# mLRS-tx-dual-base-v031-np.net
KiCad netlist of a schematic drawn in EAGLE
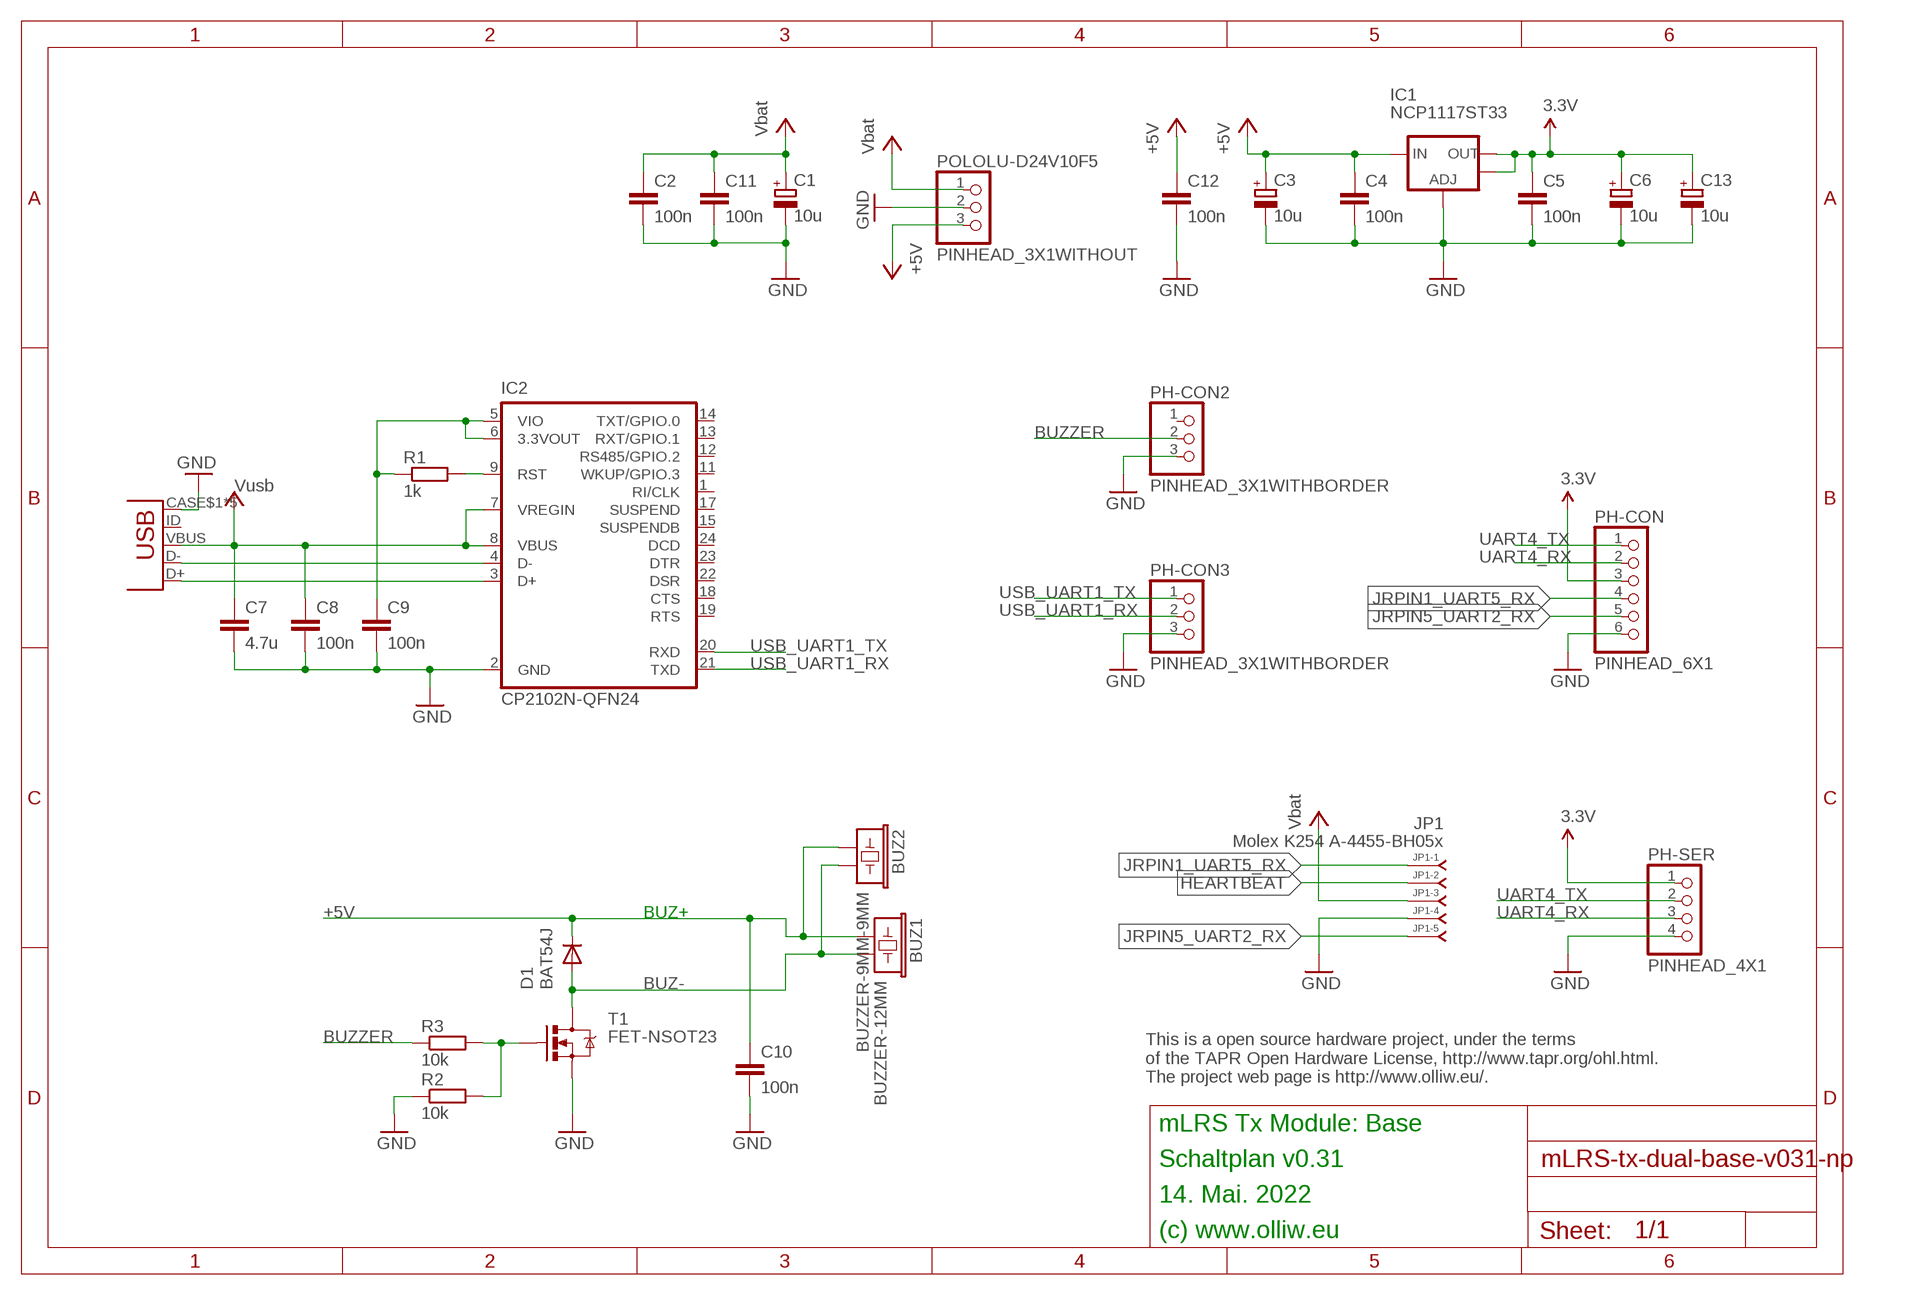
[diagram p0: schematic, sheet 1]

(export (version "E")
  (design (tool "Eeschema 10.0.6"))
  (components
    (comp (ref "BUZ1")
      (value "BUZZER-12MM")
      (footprint "eagle-import:BUZZER-12MM")
      (libsource (lib "eagle-import") (part "BUZZER-12MM"))
    )
    (comp (ref "BUZ2")
      (value "BUZZER-9MM-9MM")
      (footprint "eagle-import:BUZZER-9MM")
      (libsource (lib "eagle-import") (part "BUZZER-9MM-9MM"))
    )
    (comp (ref "C1")
      (value "10u")
      (footprint "eagle-import:SMC_A")
      (libsource (lib "eagle-import") (part "CPOL-EUSMCA"))
    )
    (comp (ref "C2")
      (value "100n")
      (footprint "eagle-import:C0603")
      (libsource (lib "eagle-import") (part "C-EUC0603"))
    )
    (comp (ref "C3")
      (value "10u")
      (footprint "eagle-import:SMC_A")
      (libsource (lib "eagle-import") (part "CPOL-EUSMCA"))
    )
    (comp (ref "C4")
      (value "100n")
      (footprint "eagle-import:C0603")
      (libsource (lib "eagle-import") (part "C-EUC0603"))
    )
    (comp (ref "C5")
      (value "100n")
      (footprint "eagle-import:C0603")
      (libsource (lib "eagle-import") (part "C-EUC0603"))
    )
    (comp (ref "C6")
      (value "10u")
      (footprint "eagle-import:SMC_A")
      (libsource (lib "eagle-import") (part "CPOL-EUSMCA"))
    )
    (comp (ref "C7")
      (value "4.7u")
      (footprint "eagle-import:C0603")
      (libsource (lib "eagle-import") (part "C-EUC0603"))
    )
    (comp (ref "C8")
      (value "100n")
      (footprint "eagle-import:C0402")
      (libsource (lib "eagle-import") (part "C-EUC0402"))
    )
    (comp (ref "C9")
      (value "100n")
      (footprint "eagle-import:C0402")
      (libsource (lib "eagle-import") (part "C-EUC0402"))
    )
    (comp (ref "C10")
      (value "100n")
      (footprint "eagle-import:C0402")
      (libsource (lib "eagle-import") (part "C-EUC0402"))
    )
    (comp (ref "C11")
      (value "100n")
      (footprint "eagle-import:C0603")
      (libsource (lib "eagle-import") (part "C-EUC0603"))
    )
    (comp (ref "C12")
      (value "100n")
      (footprint "eagle-import:C0603")
      (libsource (lib "eagle-import") (part "C-EUC0603"))
    )
    (comp (ref "C13")
      (value "10u")
      (footprint "eagle-import:SMC_A")
      (libsource (lib "eagle-import") (part "CPOL-EUSMCA"))
    )
    (comp (ref "D1")
      (value "BAT54J")
      (footprint "eagle-import:SOD110-R")
      (libsource (lib "eagle-import") (part "DIODE-SOD110-R"))
    )
    (comp (ref "IC1")
      (value "NCP1117ST33")
      (footprint "eagle-import:SOT223")
      (libsource (lib "eagle-import") (part "V_REG_LM1117SOT223"))
    )
    (comp (ref "IC2")
      (value "CP2102N-QFN24")
      (footprint "eagle-import:QFN24-CP2102N")
      (libsource (lib "eagle-import") (part "CP2102N-QFN24"))
    )
    (comp (ref "JP1")
      (value "Molex K254 A-4455-BH05x")
      (footprint "eagle-import:4455-B05")
      (libsource (lib "eagle-import") (part "4455-B05_S"))
    )
    (comp (ref "PH-CON")
      (value "PINHEAD_6X1")
      (footprint "eagle-import:PINHEAD_6X1")
      (libsource (lib "eagle-import") (part "PINHEAD_6X1"))
    )
    (comp (ref "PH-CON2")
      (value "PINHEAD_3X1WITHBORDER")
      (footprint "eagle-import:PINHEAD_3X1")
      (libsource (lib "eagle-import") (part "PINHEAD_3X1WITHBORDER"))
    )
    (comp (ref "PH-CON3")
      (value "PINHEAD_3X1WITHBORDER")
      (footprint "eagle-import:PINHEAD_3X1")
      (libsource (lib "eagle-import") (part "PINHEAD_3X1WITHBORDER"))
    )
    (comp (ref "PH-SER")
      (value "PINHEAD_4X1")
      (footprint "eagle-import:PINHEAD_4X1")
      (libsource (lib "eagle-import") (part "PINHEAD_4X1"))
    )
    (comp (ref "POLOLU-D24V10F5")
      (value "PINHEAD_3X1WITHOUT")
      (footprint "eagle-import:PINHEAD_3X1_WO")
      (libsource (lib "eagle-import") (part "PINHEAD_3X1WITHOUT"))
    )
    (comp (ref "R1")
      (value "1k")
      (footprint "eagle-import:R0402")
      (libsource (lib "eagle-import") (part "R-EU_R0402"))
    )
    (comp (ref "R2")
      (value "10k")
      (footprint "eagle-import:R0402")
      (libsource (lib "eagle-import") (part "R-EU_R0402"))
    )
    (comp (ref "R3")
      (value "10k")
      (footprint "eagle-import:R0402")
      (libsource (lib "eagle-import") (part "R-EU_R0402"))
    )
    (comp (ref "T1")
      (value "FET-NSOT23")
      (footprint "eagle-import:SOT23")
      (libsource (lib "eagle-import") (part "FET-NSOT23"))
    )
    (comp (ref "U$1")
      (value "USB-MICROB-UP-NONPLATED")
      (footprint "eagle-import:USB-MICROB-UP-NONPLATED")
      (libsource (lib "eagle-import") (part "USB-MICROB-UP-NONPLATED"))
    )
  )
  (nets
    (net (code "1") (name "+5V") (class "Default")
      (node (ref "BUZ1") (pin "+") (pinfunction "1_+") (pintype "passive"))
      (node (ref "BUZ2") (pin "+") (pinfunction "1_+") (pintype "passive"))
      (node (ref "C10") (pin "1") (pinfunction "1_1") (pintype "passive"))
      (node (ref "C12") (pin "1") (pinfunction "1_1") (pintype "passive"))
      (node (ref "C3") (pin "+") (pinfunction "+_+") (pintype "passive"))
      (node (ref "C4") (pin "1") (pinfunction "1_1") (pintype "passive"))
      (node (ref "D1") (pin "C") (pinfunction "C_C") (pintype "passive"))
      (node (ref "IC1") (pin "3") (pinfunction "IN_3") (pintype "input"))
      (node (ref "POLOLU-D24V10F5") (pin "3") (pinfunction "5_3") (pintype "passive"))
    )
    (net (code "2") (name "/BUZ-") (class "Default")
      (node (ref "BUZ1") (pin "-") (pinfunction "2_-") (pintype "passive"))
      (node (ref "BUZ2") (pin "-") (pinfunction "2_-") (pintype "passive"))
      (node (ref "D1") (pin "A") (pinfunction "A_A") (pintype "passive"))
      (node (ref "T1") (pin "3") (pinfunction "D_3") (pintype "passive"))
    )
    (net (code "3") (name "/BUZZER") (class "Default")
      (node (ref "PH-CON2") (pin "2") (pinfunction "3_2") (pintype "passive"))
      (node (ref "R3") (pin "1") (pinfunction "1_1") (pintype "passive"))
    )
    (net (code "4") (name "/UART4_RX") (class "Default")
      (node (ref "PH-CON") (pin "2") (pinfunction "2_2") (pintype "passive"))
      (node (ref "PH-SER") (pin "3") (pinfunction "3_3") (pintype "passive"))
    )
    (net (code "5") (name "/UART4_TX") (class "Default")
      (node (ref "PH-CON") (pin "1") (pinfunction "1_1") (pintype "passive"))
      (node (ref "PH-SER") (pin "2") (pinfunction "2_2") (pintype "passive"))
    )
    (net (code "6") (name "/USB_UART1_RX") (class "Default")
      (node (ref "IC2") (pin "21") (pinfunction "TXD_21") (pintype "output"))
      (node (ref "PH-CON3") (pin "2") (pinfunction "3_2") (pintype "passive"))
    )
    (net (code "7") (name "/USB_UART1_TX") (class "Default")
      (node (ref "IC2") (pin "20") (pinfunction "RXD_20") (pintype "input"))
      (node (ref "PH-CON3") (pin "1") (pinfunction "1_1") (pintype "passive"))
    )
    (net (code "8") (name "3.3V") (class "Default")
      (node (ref "C13") (pin "+") (pinfunction "+_+") (pintype "passive"))
      (node (ref "C5") (pin "1") (pinfunction "1_1") (pintype "passive"))
      (node (ref "C6") (pin "+") (pinfunction "+_+") (pintype "passive"))
      (node (ref "IC1") (pin "2") (pinfunction "OUT_2") (pintype "output"))
      (node (ref "IC1") (pin "4") (pinfunction "OUT_4") (pintype "output"))
      (node (ref "PH-CON") (pin "3") (pinfunction "3_3") (pintype "passive"))
      (node (ref "PH-SER") (pin "1") (pinfunction "1_1") (pintype "passive"))
    )
    (net (code "9") (name "GND") (class "Default")
      (node (ref "C1") (pin "-") (pinfunction "-_-") (pintype "passive"))
      (node (ref "C10") (pin "2") (pinfunction "2_2") (pintype "passive"))
      (node (ref "C11") (pin "2") (pinfunction "2_2") (pintype "passive"))
      (node (ref "C12") (pin "2") (pinfunction "2_2") (pintype "passive"))
      (node (ref "C13") (pin "-") (pinfunction "-_-") (pintype "passive"))
      (node (ref "C2") (pin "2") (pinfunction "2_2") (pintype "passive"))
      (node (ref "C3") (pin "-") (pinfunction "-_-") (pintype "passive"))
      (node (ref "C4") (pin "2") (pinfunction "2_2") (pintype "passive"))
      (node (ref "C5") (pin "2") (pinfunction "2_2") (pintype "passive"))
      (node (ref "C6") (pin "-") (pinfunction "-_-") (pintype "passive"))
      (node (ref "C7") (pin "2") (pinfunction "2_2") (pintype "passive"))
      (node (ref "C8") (pin "2") (pinfunction "2_2") (pintype "passive"))
      (node (ref "C9") (pin "2") (pinfunction "2_2") (pintype "passive"))
      (node (ref "IC1") (pin "1") (pinfunction "ADJ_1") (pintype "input"))
      (node (ref "IC2") (pin "2") (pinfunction "GND_2") (pintype "power_in"))
      (node (ref "JP1") (pin "4") (pinfunction "J_4") (pintype "passive"))
      (node (ref "PH-CON") (pin "6") (pinfunction "6_6") (pintype "passive"))
      (node (ref "PH-CON2") (pin "3") (pinfunction "5_3") (pintype "passive"))
      (node (ref "PH-CON3") (pin "3") (pinfunction "5_3") (pintype "passive"))
      (node (ref "PH-SER") (pin "4") (pinfunction "4_4") (pintype "passive"))
      (node (ref "POLOLU-D24V10F5") (pin "2") (pinfunction "3_2") (pintype "passive"))
      (node (ref "R2") (pin "1") (pinfunction "1_1") (pintype "passive"))
      (node (ref "T1") (pin "2") (pinfunction "S_2") (pintype "passive"))
      (node (ref "U$1") (pin "CASE$1") (pinfunction "GND_CASE$1") (pintype "bidirectional"))
      (node (ref "U$1") (pin "CASE$2") (pinfunction "GND_CASE$2") (pintype "bidirectional"))
      (node (ref "U$1") (pin "CASE$3") (pinfunction "GND_CASE$3") (pintype "bidirectional"))
      (node (ref "U$1") (pin "CASE$4") (pinfunction "GND_CASE$4") (pintype "bidirectional"))
      (node (ref "U$1") (pin "GND") (pinfunction "GND_GND") (pintype "bidirectional"))
    )
    (net (code "10") (name "HEARTBEAT") (class "Default")
      (node (ref "JP1") (pin "2") (pinfunction "J_2") (pintype "passive"))
    )
    (net (code "11") (name "JRPIN1_UART5_RX") (class "Default")
      (node (ref "JP1") (pin "1") (pinfunction "J_1") (pintype "passive"))
      (node (ref "PH-CON") (pin "4") (pinfunction "4_4") (pintype "passive"))
    )
    (net (code "12") (name "JRPIN5_UART2_RX") (class "Default")
      (node (ref "JP1") (pin "5") (pinfunction "J_5") (pintype "passive"))
      (node (ref "PH-CON") (pin "5") (pinfunction "5_5") (pintype "passive"))
    )
    (net (code "13") (name "Net-(IC2-3.3VOUT)") (class "Default")
      (node (ref "C9") (pin "1") (pinfunction "1_1") (pintype "passive"))
      (node (ref "IC2") (pin "5") (pinfunction "VIO_5") (pintype "power_in"))
      (node (ref "IC2") (pin "6") (pinfunction "3.3VOUT_6") (pintype "power_in"))
      (node (ref "R1") (pin "1") (pinfunction "1_1") (pintype "passive"))
    )
    (net (code "14") (name "Net-(IC2-D+)") (class "Default")
      (node (ref "IC2") (pin "3") (pinfunction "D+_3") (pintype "bidirectional"))
      (node (ref "U$1") (pin "D+") (pinfunction "D+_D+") (pintype "bidirectional"))
    )
    (net (code "15") (name "Net-(IC2-D-)") (class "Default")
      (node (ref "IC2") (pin "4") (pinfunction "D-_4") (pintype "bidirectional"))
      (node (ref "U$1") (pin "D-") (pinfunction "D-_D-") (pintype "bidirectional"))
    )
    (net (code "16") (name "Net-(IC2-RST)") (class "Default")
      (node (ref "IC2") (pin "9") (pinfunction "RST_9") (pintype "input"))
      (node (ref "R1") (pin "2") (pinfunction "2_2") (pintype "passive"))
    )
    (net (code "17") (name "Net-(T1-G)") (class "Default")
      (node (ref "R2") (pin "2") (pinfunction "2_2") (pintype "passive"))
      (node (ref "R3") (pin "2") (pinfunction "2_2") (pintype "passive"))
      (node (ref "T1") (pin "1") (pinfunction "G_1") (pintype "passive"))
    )
    (net (code "18") (name "Vbat") (class "Default")
      (node (ref "C1") (pin "+") (pinfunction "+_+") (pintype "passive"))
      (node (ref "C11") (pin "1") (pinfunction "1_1") (pintype "passive"))
      (node (ref "C2") (pin "1") (pinfunction "1_1") (pintype "passive"))
      (node (ref "JP1") (pin "3") (pinfunction "J_3") (pintype "passive"))
      (node (ref "POLOLU-D24V10F5") (pin "1") (pinfunction "1_1") (pintype "passive"))
    )
    (net (code "19") (name "Vusb") (class "Default")
      (node (ref "C7") (pin "1") (pinfunction "1_1") (pintype "passive"))
      (node (ref "C8") (pin "1") (pinfunction "1_1") (pintype "passive"))
      (node (ref "IC2") (pin "7") (pinfunction "VREGIN_7") (pintype "power_in"))
      (node (ref "IC2") (pin "8") (pinfunction "VBUS_8") (pintype "input"))
      (node (ref "U$1") (pin "VBUS") (pinfunction "VBUS_VBUS") (pintype "bidirectional"))
    )
    (net (code "20") (name "unconnected-(IC2-CTS-Pad18)") (class "Default")
      (node (ref "IC2") (pin "18") (pinfunction "CTS_18") (pintype "input"))
    )
    (net (code "21") (name "unconnected-(IC2-DCD-Pad24)") (class "Default")
      (node (ref "IC2") (pin "24") (pinfunction "DCD_24") (pintype "input"))
    )
    (net (code "22") (name "unconnected-(IC2-DSR-Pad22)") (class "Default")
      (node (ref "IC2") (pin "22") (pinfunction "DSR_22") (pintype "input"))
    )
    (net (code "23") (name "unconnected-(IC2-DTR-Pad23)") (class "Default")
      (node (ref "IC2") (pin "23") (pinfunction "DTR_23") (pintype "output"))
    )
    (net (code "24") (name "unconnected-(IC2-RI{slash}CLK-Pad1)") (class "Default")
      (node (ref "IC2") (pin "1") (pinfunction "RI/CLK_1") (pintype "input"))
    )
    (net (code "25") (name "unconnected-(IC2-RS485{slash}GPIO.2-Pad12)") (class "Default")
      (node (ref "IC2") (pin "12") (pinfunction "RS485/GPIO.2_12") (pintype "bidirectional"))
    )
    (net (code "26") (name "unconnected-(IC2-RTS-Pad19)") (class "Default")
      (node (ref "IC2") (pin "19") (pinfunction "RTS_19") (pintype "output"))
    )
    (net (code "27") (name "unconnected-(IC2-RXT{slash}GPIO.1-Pad13)") (class "Default")
      (node (ref "IC2") (pin "13") (pinfunction "RXT/GPIO.1_13") (pintype "bidirectional"))
    )
    (net (code "28") (name "unconnected-(IC2-SUSPEND-Pad17)") (class "Default")
      (node (ref "IC2") (pin "17") (pinfunction "SUSPEND_17") (pintype "output"))
    )
    (net (code "29") (name "unconnected-(IC2-SUSPENDB-Pad15)") (class "Default")
      (node (ref "IC2") (pin "15") (pinfunction "SUSPENDB_15") (pintype "output"))
    )
    (net (code "30") (name "unconnected-(IC2-TXT{slash}GPIO.0-Pad14)") (class "Default")
      (node (ref "IC2") (pin "14") (pinfunction "TXT/GPIO.0_14") (pintype "bidirectional"))
    )
    (net (code "31") (name "unconnected-(IC2-WKUP{slash}GPIO.3-Pad11)") (class "Default")
      (node (ref "IC2") (pin "11") (pinfunction "WKUP/GPIO.3_11") (pintype "bidirectional"))
    )
    (net (code "32") (name "unconnected-(PH-CON2-Pad1)") (class "Default")
      (node (ref "PH-CON2") (pin "1") (pinfunction "1_1") (pintype "passive"))
    )
    (net (code "33") (name "unconnected-(U$1-PadID)") (class "Default")
      (node (ref "U$1") (pin "ID") (pinfunction "ID_ID") (pintype "bidirectional"))
    )
  )
)
